# RES.net
KiCad netlist of a schematic drawn in EAGLE
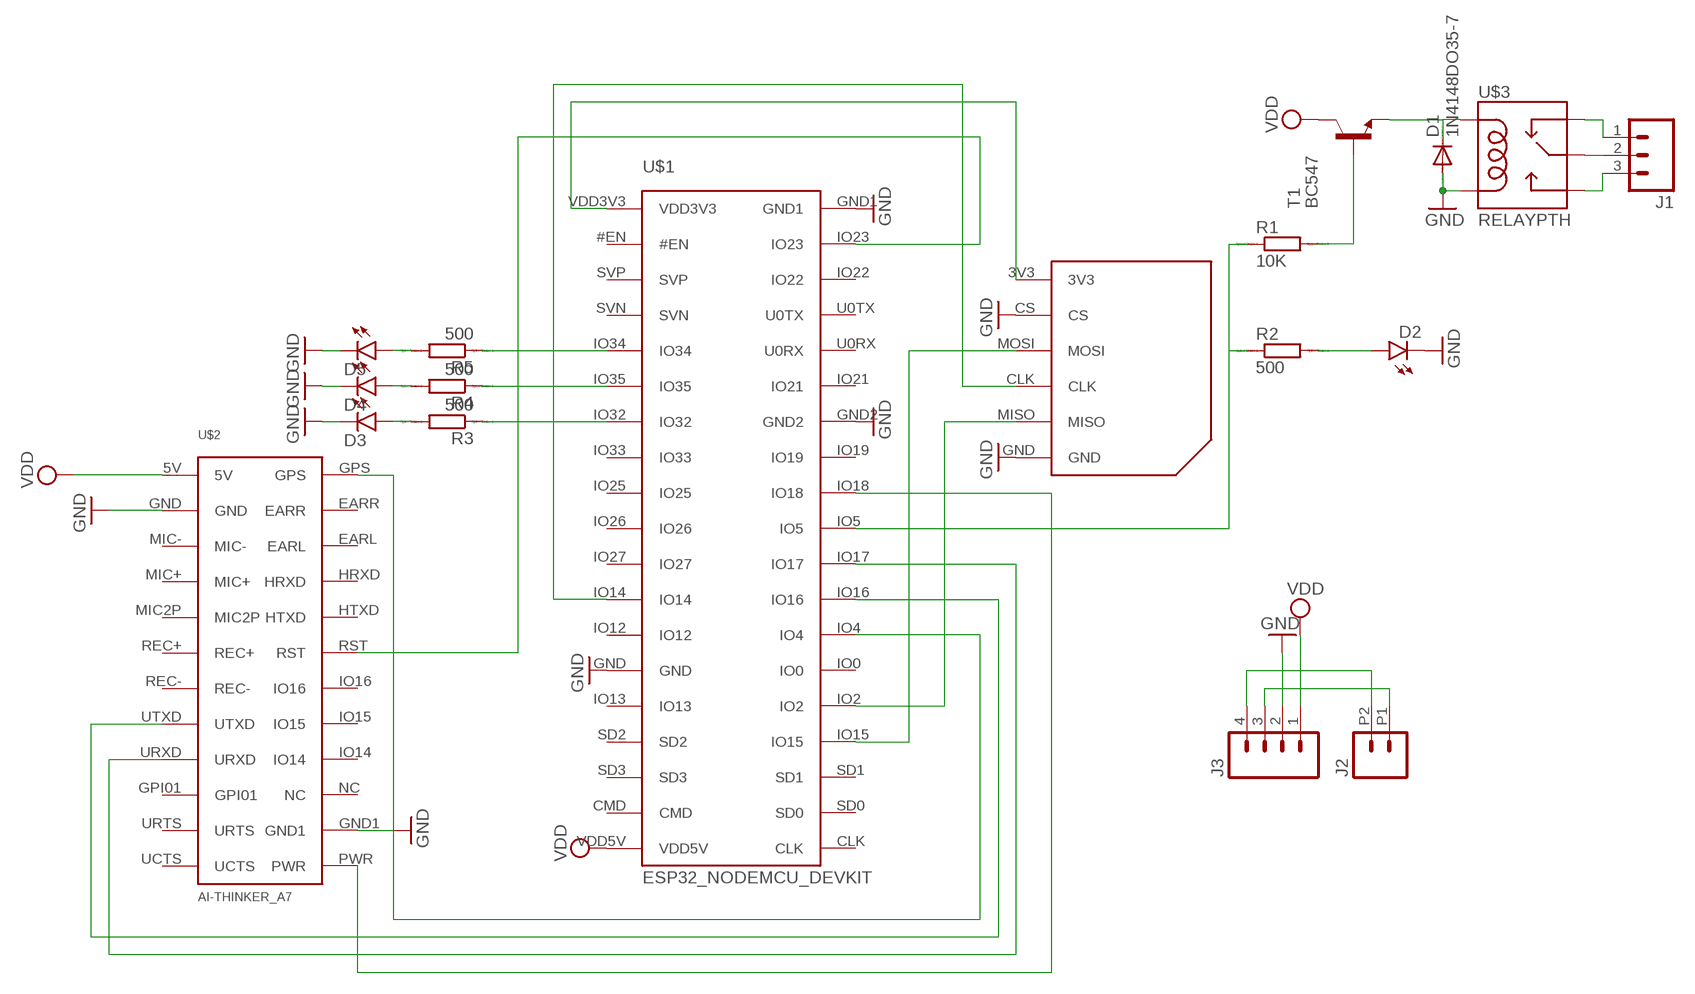
[diagram p0: schematic, sheet 1]

(export (version "E")
  (design (tool "Eeschema 10.0.6"))
  (components
    (comp (ref "D1")
      (value "1N4148DO35-7")
      (footprint "eagle-import:DO35-7")
      (libsource (lib "eagle-import") (part "1N4148DO35-7"))
    )
    (comp (ref "D2")
      (value "LED3MM")
      (footprint "eagle-import:LED3MM")
      (libsource (lib "eagle-import") (part "LED3MM"))
    )
    (comp (ref "D3")
      (value "LED3MM")
      (footprint "eagle-import:LED3MM")
      (libsource (lib "eagle-import") (part "LED3MM"))
    )
    (comp (ref "D4")
      (value "LED3MM")
      (footprint "eagle-import:LED3MM")
      (libsource (lib "eagle-import") (part "LED3MM"))
    )
    (comp (ref "D5")
      (value "LED3MM")
      (footprint "eagle-import:LED3MM")
      (libsource (lib "eagle-import") (part "LED3MM"))
    )
    (comp (ref "J1")
      (value "M03-SCREW-5MM")
      (footprint "eagle-import:SCREWTERMINAL-5MM-3")
      (libsource (lib "eagle-import") (part "M03-SCREW-5MM"))
    )
    (comp (ref "J2")
      (value "M022.54MM_SCREWTERM")
      (footprint "eagle-import:1X02_2.54_SCREWTERM")
      (libsource (lib "eagle-import") (part "M022.54MM_SCREWTERM"))
    )
    (comp (ref "J3")
      (value "M04SCREW")
      (footprint "eagle-import:SCREWTERMINAL-3.5MM-4")
      (libsource (lib "eagle-import") (part "M04SCREW"))
    )
    (comp (ref "R1")
      (value "10K")
      (footprint "eagle-import:0204_7")
      (libsource (lib "eagle-import") (part "R0204/7"))
    )
    (comp (ref "R2")
      (value "500")
      (footprint "eagle-import:0204_7")
      (libsource (lib "eagle-import") (part "R0204/7"))
    )
    (comp (ref "R3")
      (value "500")
      (footprint "eagle-import:0204_7")
      (libsource (lib "eagle-import") (part "R0204/7"))
    )
    (comp (ref "R4")
      (value "500")
      (footprint "eagle-import:0204_7")
      (libsource (lib "eagle-import") (part "R0204/7"))
    )
    (comp (ref "R5")
      (value "500")
      (footprint "eagle-import:0204_7")
      (libsource (lib "eagle-import") (part "R0204/7"))
    )
    (comp (ref "T1")
      (value "BC547")
      (footprint "eagle-import:TO92")
      (libsource (lib "eagle-import") (part "BC547"))
    )
    (comp (ref "U$1")
      (value "ESP32_NODEMCU_DEVKIT")
      (footprint "eagle-import:ESP32_NODEMCU_PACKAGE")
      (libsource (lib "eagle-import") (part "ESP32_NODEMCU_DEVKIT"))
    )
    (comp (ref "U$2")
      (value "AI-THINKER_A7")
      (footprint "eagle-import:AI-THINKER_A7_PAC")
      (libsource (lib "eagle-import") (part "AI-THINKER_A7"))
    )
    (comp (ref "U$3")
      (value "RELAYPTH")
      (footprint "eagle-import:SRD-05VDC-SL-C")
      (libsource (lib "eagle-import") (part "RELAYPTH"))
    )
    (comp (ref "U$4")
      (value "SD-CARD_BREAKOUT")
      (footprint "eagle-import:SD-CARD_BREAKOUT_PACK")
      (libsource (lib "eagle-import") (part "SD-CARD_BREAKOUT"))
    )
  )
  (nets
    (net (code "1") (name "GND") (class "Default")
      (node (ref "D1") (pin "A") (pinfunction "A_A") (pintype "passive"))
      (node (ref "D2") (pin "K") (pinfunction "C_K") (pintype "passive"))
      (node (ref "D3") (pin "K") (pinfunction "C_K") (pintype "passive"))
      (node (ref "D4") (pin "K") (pinfunction "C_K") (pintype "passive"))
      (node (ref "D5") (pin "K") (pinfunction "C_K") (pintype "passive"))
      (node (ref "J3") (pin "2") (pinfunction "2_2") (pintype "passive"))
      (node (ref "U$1") (pin "GND") (pinfunction "GND_GND") (pintype "bidirectional"))
      (node (ref "U$1") (pin "GND1") (pinfunction "GND1_GND1") (pintype "bidirectional"))
      (node (ref "U$1") (pin "GND2") (pinfunction "GND2_GND2") (pintype "bidirectional"))
      (node (ref "U$2") (pin "GND") (pinfunction "GND_GND") (pintype "bidirectional"))
      (node (ref "U$2") (pin "GND1") (pinfunction "GND1_GND1") (pintype "bidirectional"))
      (node (ref "U$3") (pin "COIL0") (pinfunction "COIL0_COIL0") (pintype "bidirectional"))
      (node (ref "U$4") (pin "CS") (pinfunction "CS_CS") (pintype "bidirectional"))
      (node (ref "U$4") (pin "GND") (pinfunction "GND_GND") (pintype "bidirectional"))
    )
    (net (code "2") (name "Net-(D2-PadA)") (class "Default")
      (node (ref "D2") (pin "A") (pinfunction "A_A") (pintype "passive"))
      (node (ref "R2") (pin "2") (pinfunction "2_2") (pintype "passive"))
    )
    (net (code "3") (name "Net-(D3-PadA)") (class "Default")
      (node (ref "D3") (pin "A") (pinfunction "A_A") (pintype "passive"))
      (node (ref "R3") (pin "2") (pinfunction "2_2") (pintype "passive"))
    )
    (net (code "4") (name "Net-(D4-PadA)") (class "Default")
      (node (ref "D4") (pin "A") (pinfunction "A_A") (pintype "passive"))
      (node (ref "R4") (pin "2") (pinfunction "2_2") (pintype "passive"))
    )
    (net (code "5") (name "Net-(D5-PadA)") (class "Default")
      (node (ref "D5") (pin "A") (pinfunction "A_A") (pintype "passive"))
      (node (ref "R5") (pin "2") (pinfunction "2_2") (pintype "passive"))
    )
    (net (code "6") (name "Net-(J1-Pad2)") (class "Default")
      (node (ref "J1") (pin "2") (pinfunction "2_2") (pintype "passive"))
      (node (ref "U$3") (pin "SWCOMMON") (pinfunction "SWCOMMON_SWCOMMON") (pintype "bidirectional"))
    )
    (net (code "7") (name "Net-(J1-Pad3)") (class "Default")
      (node (ref "J1") (pin "3") (pinfunction "3_3") (pintype "passive"))
      (node (ref "U$3") (pin "SWOPEN") (pinfunction "SWOPEN_SWOPEN") (pintype "bidirectional"))
    )
    (net (code "8") (name "Net-(J2-1)") (class "Default")
      (node (ref "J2") (pin "P1") (pinfunction "1_P1") (pintype "passive"))
      (node (ref "J3") (pin "3") (pinfunction "3_3") (pintype "passive"))
    )
    (net (code "9") (name "Net-(J2-2)") (class "Default")
      (node (ref "J2") (pin "P2") (pinfunction "2_P2") (pintype "passive"))
      (node (ref "J3") (pin "4") (pinfunction "4_4") (pintype "passive"))
    )
    (net (code "10") (name "Net-(R1-Pad1)") (class "Default")
      (node (ref "R1") (pin "1") (pinfunction "1_1") (pintype "passive"))
      (node (ref "R2") (pin "1") (pinfunction "1_1") (pintype "passive"))
      (node (ref "U$1") (pin "IO5") (pinfunction "IO5_IO5") (pintype "bidirectional"))
    )
    (net (code "11") (name "Net-(R3-Pad1)") (class "Default")
      (node (ref "R3") (pin "1") (pinfunction "1_1") (pintype "passive"))
      (node (ref "U$1") (pin "IO32") (pinfunction "IO32_IO32") (pintype "bidirectional"))
    )
    (net (code "12") (name "Net-(R4-Pad1)") (class "Default")
      (node (ref "R4") (pin "1") (pinfunction "1_1") (pintype "passive"))
      (node (ref "U$1") (pin "IO35") (pinfunction "IO35_IO35") (pintype "bidirectional"))
    )
    (net (code "13") (name "Net-(R5-Pad1)") (class "Default")
      (node (ref "R5") (pin "1") (pinfunction "1_1") (pintype "passive"))
      (node (ref "U$1") (pin "IO34") (pinfunction "IO34_IO34") (pintype "bidirectional"))
    )
    (net (code "14") (name "Net-(T1-B)") (class "Default")
      (node (ref "R1") (pin "2") (pinfunction "2_2") (pintype "passive"))
      (node (ref "T1") (pin "2") (pinfunction "B_2") (pintype "passive"))
    )
    (net (code "15") (name "Net-(T1-E)") (class "Default")
      (node (ref "D1") (pin "C") (pinfunction "C_C") (pintype "passive"))
      (node (ref "T1") (pin "1") (pinfunction "E_1") (pintype "passive"))
      (node (ref "U$3") (pin "COIL1") (pinfunction "COIL1_COIL1") (pintype "bidirectional"))
    )
    (net (code "16") (name "Net-(U$1-PadIO2)") (class "Default")
      (node (ref "U$1") (pin "IO2") (pinfunction "IO2_IO2") (pintype "bidirectional"))
      (node (ref "U$4") (pin "MISO") (pinfunction "MISO_MISO") (pintype "bidirectional"))
    )
    (net (code "17") (name "Net-(U$1-PadIO4)") (class "Default")
      (node (ref "U$1") (pin "IO4") (pinfunction "IO4_IO4") (pintype "bidirectional"))
      (node (ref "U$2") (pin "GPS") (pinfunction "GPS_GPS") (pintype "bidirectional"))
    )
    (net (code "18") (name "Net-(U$1-PadIO14)") (class "Default")
      (node (ref "U$1") (pin "IO14") (pinfunction "IO14_IO14") (pintype "bidirectional"))
      (node (ref "U$4") (pin "CLK") (pinfunction "CLK_CLK") (pintype "bidirectional"))
    )
    (net (code "19") (name "Net-(U$1-PadIO15)") (class "Default")
      (node (ref "U$1") (pin "IO15") (pinfunction "IO15_IO15") (pintype "bidirectional"))
      (node (ref "U$4") (pin "MOSI") (pinfunction "MOSI_MOSI") (pintype "bidirectional"))
    )
    (net (code "20") (name "Net-(U$1-PadIO16)") (class "Default")
      (node (ref "U$1") (pin "IO16") (pinfunction "IO16_IO16") (pintype "bidirectional"))
      (node (ref "U$2") (pin "UTXD") (pinfunction "UTXD_UTXD") (pintype "bidirectional"))
    )
    (net (code "21") (name "Net-(U$1-PadIO17)") (class "Default")
      (node (ref "U$1") (pin "IO17") (pinfunction "IO17_IO17") (pintype "bidirectional"))
      (node (ref "U$2") (pin "URXD") (pinfunction "URXD_URXD") (pintype "bidirectional"))
    )
    (net (code "22") (name "Net-(U$1-PadIO18)") (class "Default")
      (node (ref "U$1") (pin "IO18") (pinfunction "IO18_IO18") (pintype "bidirectional"))
      (node (ref "U$2") (pin "PWR") (pinfunction "PWR_PWR") (pintype "bidirectional"))
    )
    (net (code "23") (name "Net-(U$1-PadIO23)") (class "Default")
      (node (ref "U$1") (pin "IO23") (pinfunction "IO23_IO23") (pintype "bidirectional"))
      (node (ref "U$2") (pin "RST") (pinfunction "RST_RST") (pintype "bidirectional"))
    )
    (net (code "24") (name "Net-(U$1-PadVDD3V3)") (class "Default")
      (node (ref "U$1") (pin "VDD3V3") (pinfunction "VDD3V3_VDD3V3") (pintype "bidirectional"))
      (node (ref "U$4") (pin "3V3") (pinfunction "3V3_3V3") (pintype "bidirectional"))
    )
    (net (code "25") (name "Net-(U$3-SWCLOSE)") (class "Default")
      (node (ref "J1") (pin "1") (pinfunction "1_1") (pintype "passive"))
      (node (ref "U$3") (pin "SWCLOSED") (pinfunction "SWCLOSE_SWCLOSED") (pintype "bidirectional"))
    )
    (net (code "26") (name "VDD") (class "Default")
      (node (ref "J3") (pin "1") (pinfunction "1_1") (pintype "passive"))
      (node (ref "T1") (pin "3") (pinfunction "C_3") (pintype "passive"))
      (node (ref "U$1") (pin "VDD5V") (pinfunction "VDD5V_VDD5V") (pintype "bidirectional"))
      (node (ref "U$2") (pin "5V") (pinfunction "5V_5V") (pintype "bidirectional"))
    )
    (net (code "27") (name "unconnected-(U$1-Pad#EN)") (class "Default")
      (node (ref "U$1") (pin "#EN") (pinfunction "#EN_#EN") (pintype "bidirectional"))
    )
    (net (code "28") (name "unconnected-(U$1-PadCLK)") (class "Default")
      (node (ref "U$1") (pin "CLK") (pinfunction "CLK_CLK") (pintype "bidirectional"))
    )
    (net (code "29") (name "unconnected-(U$1-PadCMD)") (class "Default")
      (node (ref "U$1") (pin "CMD") (pinfunction "CMD_CMD") (pintype "bidirectional"))
    )
    (net (code "30") (name "unconnected-(U$1-PadIO0)") (class "Default")
      (node (ref "U$1") (pin "IO0") (pinfunction "IO0_IO0") (pintype "bidirectional"))
    )
    (net (code "31") (name "unconnected-(U$1-PadIO12)") (class "Default")
      (node (ref "U$1") (pin "IO12") (pinfunction "IO12_IO12") (pintype "bidirectional"))
    )
    (net (code "32") (name "unconnected-(U$1-PadIO13)") (class "Default")
      (node (ref "U$1") (pin "IO13") (pinfunction "IO13_IO13") (pintype "bidirectional"))
    )
    (net (code "33") (name "unconnected-(U$1-PadIO19)") (class "Default")
      (node (ref "U$1") (pin "IO19") (pinfunction "IO19_IO19") (pintype "bidirectional"))
    )
    (net (code "34") (name "unconnected-(U$1-PadIO21)") (class "Default")
      (node (ref "U$1") (pin "IO21") (pinfunction "IO21_IO21") (pintype "bidirectional"))
    )
    (net (code "35") (name "unconnected-(U$1-PadIO22)") (class "Default")
      (node (ref "U$1") (pin "IO22") (pinfunction "IO22_IO22") (pintype "bidirectional"))
    )
    (net (code "36") (name "unconnected-(U$1-PadIO25)") (class "Default")
      (node (ref "U$1") (pin "IO25") (pinfunction "IO25_IO25") (pintype "bidirectional"))
    )
    (net (code "37") (name "unconnected-(U$1-PadIO26)") (class "Default")
      (node (ref "U$1") (pin "IO26") (pinfunction "IO26_IO26") (pintype "bidirectional"))
    )
    (net (code "38") (name "unconnected-(U$1-PadIO27)") (class "Default")
      (node (ref "U$1") (pin "IO27") (pinfunction "IO27_IO27") (pintype "bidirectional"))
    )
    (net (code "39") (name "unconnected-(U$1-PadIO33)") (class "Default")
      (node (ref "U$1") (pin "IO33") (pinfunction "IO33_IO33") (pintype "bidirectional"))
    )
    (net (code "40") (name "unconnected-(U$1-PadSD0)") (class "Default")
      (node (ref "U$1") (pin "SD0") (pinfunction "SD0_SD0") (pintype "bidirectional"))
    )
    (net (code "41") (name "unconnected-(U$1-PadSD1)") (class "Default")
      (node (ref "U$1") (pin "SD1") (pinfunction "SD1_SD1") (pintype "bidirectional"))
    )
    (net (code "42") (name "unconnected-(U$1-PadSD2)") (class "Default")
      (node (ref "U$1") (pin "SD2") (pinfunction "SD2_SD2") (pintype "bidirectional"))
    )
    (net (code "43") (name "unconnected-(U$1-PadSD3)") (class "Default")
      (node (ref "U$1") (pin "SD3") (pinfunction "SD3_SD3") (pintype "bidirectional"))
    )
    (net (code "44") (name "unconnected-(U$1-PadSVN)") (class "Default")
      (node (ref "U$1") (pin "SVN") (pinfunction "SVN_SVN") (pintype "bidirectional"))
    )
    (net (code "45") (name "unconnected-(U$1-PadSVP)") (class "Default")
      (node (ref "U$1") (pin "SVP") (pinfunction "SVP_SVP") (pintype "bidirectional"))
    )
    (net (code "46") (name "unconnected-(U$1-PadU0RX)") (class "Default")
      (node (ref "U$1") (pin "U0RX") (pinfunction "U0RX_U0RX") (pintype "bidirectional"))
    )
    (net (code "47") (name "unconnected-(U$1-PadU0TX)") (class "Default")
      (node (ref "U$1") (pin "U0TX") (pinfunction "U0TX_U0TX") (pintype "bidirectional"))
    )
    (net (code "48") (name "unconnected-(U$2-PadEARL)") (class "Default")
      (node (ref "U$2") (pin "EARL") (pinfunction "EARL_EARL") (pintype "bidirectional"))
    )
    (net (code "49") (name "unconnected-(U$2-PadEARR)") (class "Default")
      (node (ref "U$2") (pin "EARR") (pinfunction "EARR_EARR") (pintype "bidirectional"))
    )
    (net (code "50") (name "unconnected-(U$2-PadGPI01)") (class "Default")
      (node (ref "U$2") (pin "GPI01") (pinfunction "GPI01_GPI01") (pintype "bidirectional"))
    )
    (net (code "51") (name "unconnected-(U$2-PadHRXD)") (class "Default")
      (node (ref "U$2") (pin "HRXD") (pinfunction "HRXD_HRXD") (pintype "bidirectional"))
    )
    (net (code "52") (name "unconnected-(U$2-PadHTXD)") (class "Default")
      (node (ref "U$2") (pin "HTXD") (pinfunction "HTXD_HTXD") (pintype "bidirectional"))
    )
    (net (code "53") (name "unconnected-(U$2-PadIO14)") (class "Default")
      (node (ref "U$2") (pin "IO14") (pinfunction "IO14_IO14") (pintype "bidirectional"))
    )
    (net (code "54") (name "unconnected-(U$2-PadIO15)") (class "Default")
      (node (ref "U$2") (pin "IO15") (pinfunction "IO15_IO15") (pintype "bidirectional"))
    )
    (net (code "55") (name "unconnected-(U$2-PadIO16)") (class "Default")
      (node (ref "U$2") (pin "IO16") (pinfunction "IO16_IO16") (pintype "bidirectional"))
    )
    (net (code "56") (name "unconnected-(U$2-PadMIC+)") (class "Default")
      (node (ref "U$2") (pin "MIC+") (pinfunction "MIC+_MIC+") (pintype "bidirectional"))
    )
    (net (code "57") (name "unconnected-(U$2-PadMIC-)") (class "Default")
      (node (ref "U$2") (pin "MIC-") (pinfunction "MIC-_MIC-") (pintype "bidirectional"))
    )
    (net (code "58") (name "unconnected-(U$2-PadMIC2P)") (class "Default")
      (node (ref "U$2") (pin "MIC2P") (pinfunction "MIC2P_MIC2P") (pintype "bidirectional"))
    )
    (net (code "59") (name "unconnected-(U$2-PadNC)") (class "Default")
      (node (ref "U$2") (pin "NC") (pinfunction "NC_NC") (pintype "bidirectional"))
    )
    (net (code "60") (name "unconnected-(U$2-PadREC+)") (class "Default")
      (node (ref "U$2") (pin "REC+") (pinfunction "REC+_REC+") (pintype "bidirectional"))
    )
    (net (code "61") (name "unconnected-(U$2-PadREC-)") (class "Default")
      (node (ref "U$2") (pin "REC-") (pinfunction "REC-_REC-") (pintype "bidirectional"))
    )
    (net (code "62") (name "unconnected-(U$2-PadUCTS)") (class "Default")
      (node (ref "U$2") (pin "UCTS") (pinfunction "UCTS_UCTS") (pintype "bidirectional"))
    )
    (net (code "63") (name "unconnected-(U$2-PadURTS)") (class "Default")
      (node (ref "U$2") (pin "URTS") (pinfunction "URTS_URTS") (pintype "bidirectional"))
    )
  )
)
